# main.net
KiCad netlist of a schematic drawn in EAGLE
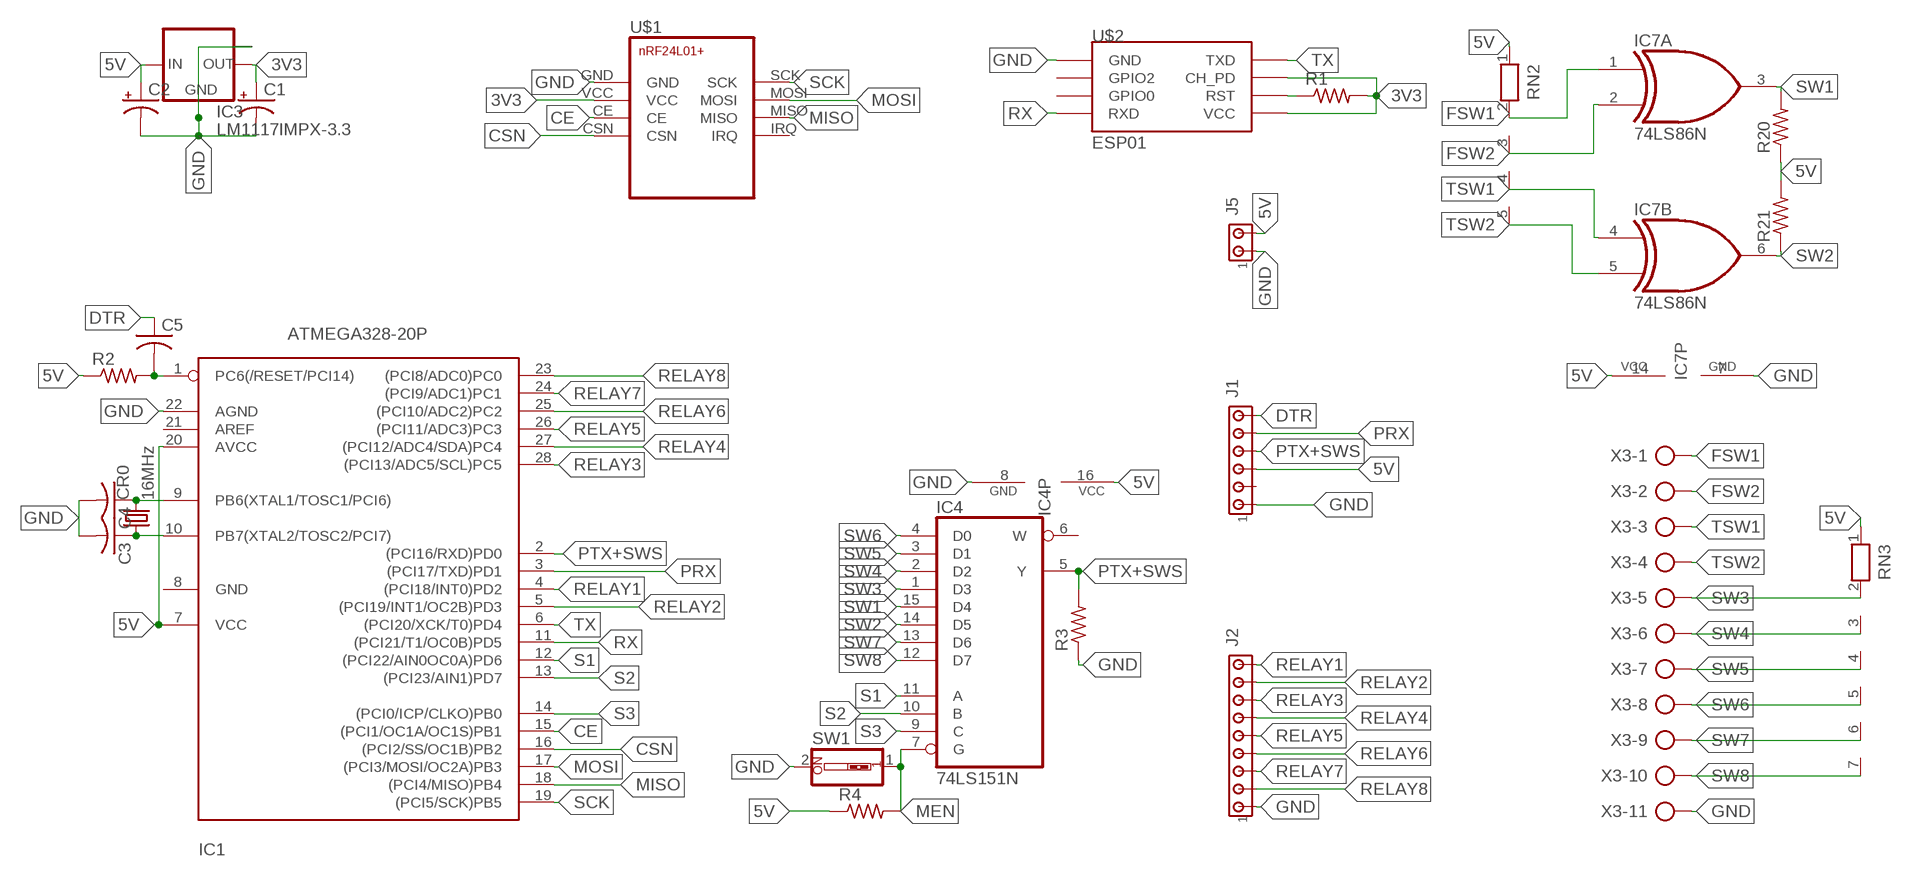
[diagram p0: schematic, sheet 1]
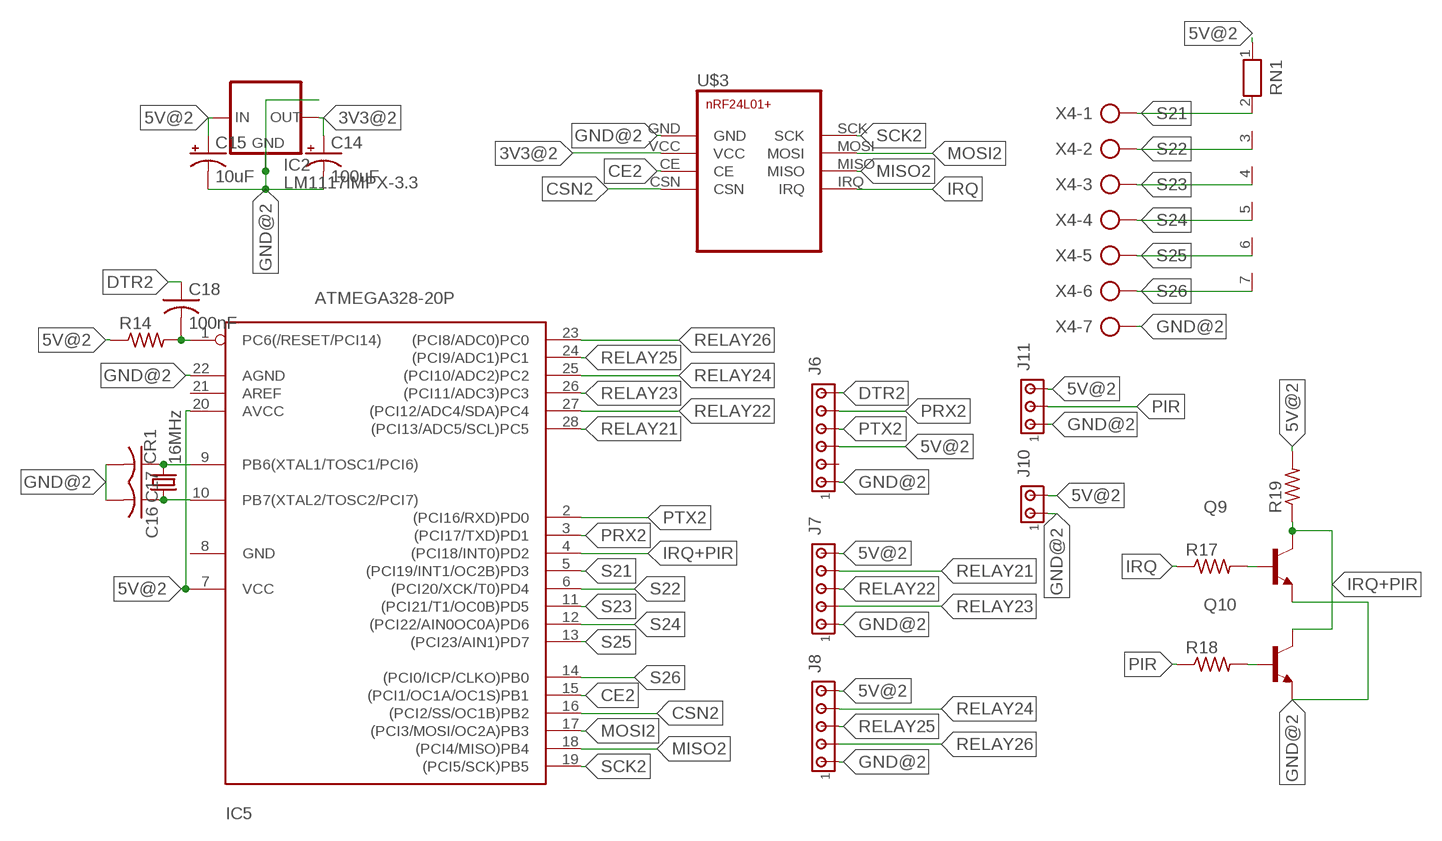
[diagram p1: schematic, sheet 2]
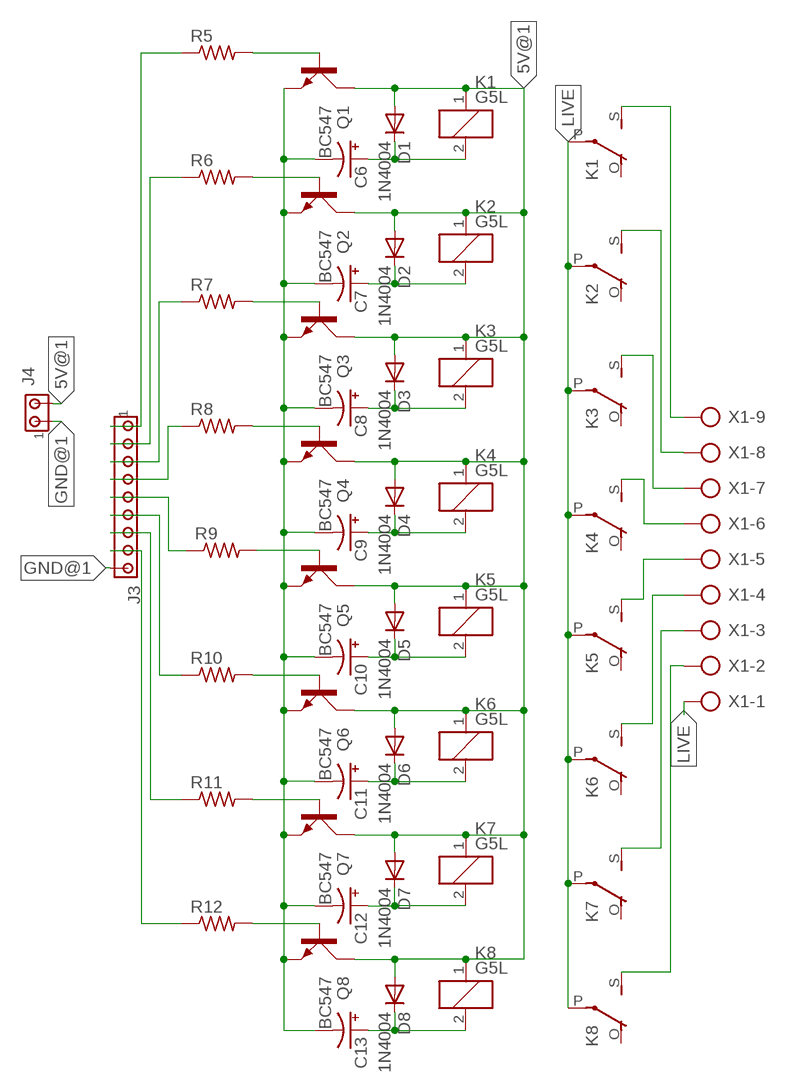
[diagram p2: schematic, sheet 3]
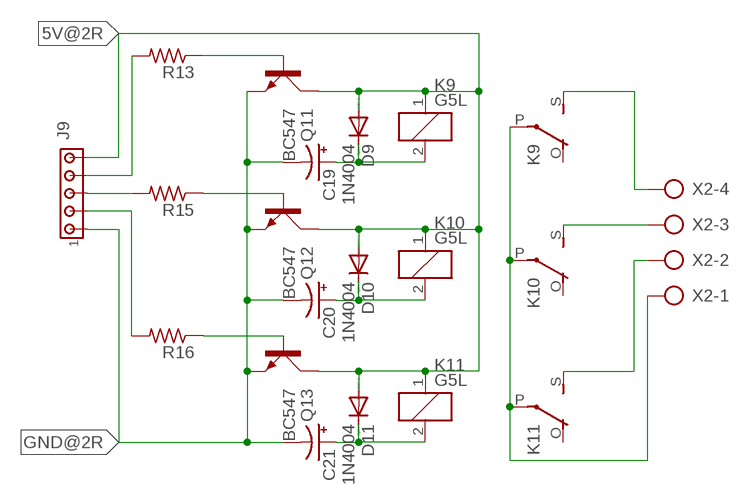
[diagram p3: schematic, sheet 4]

(export (version "E")
  (design (tool "Eeschema 10.0.6"))
  (components
    (comp (ref "C19")
      (value "CPOL-USE2.5-6")
      (footprint "eagle-import:E2,5-6")
      (libsource (lib "eagle-import") (part "CPOL-USE2.5-6"))
    )
    (comp (ref "C20")
      (value "CPOL-USE2.5-6")
      (footprint "eagle-import:E2,5-6")
      (libsource (lib "eagle-import") (part "CPOL-USE2.5-6"))
    )
    (comp (ref "C21")
      (value "CPOL-USE2.5-6")
      (footprint "eagle-import:E2,5-6")
      (libsource (lib "eagle-import") (part "CPOL-USE2.5-6"))
    )
    (comp (ref "D9")
      (value "1N4004")
      (footprint "eagle-import:DO41-10")
      (libsource (lib "eagle-import") (part "diode_210_1N4004"))
    )
    (comp (ref "D10")
      (value "1N4004")
      (footprint "eagle-import:DO41-10")
      (libsource (lib "eagle-import") (part "diode_210_1N4004"))
    )
    (comp (ref "D11")
      (value "1N4004")
      (footprint "eagle-import:DO41-10")
      (libsource (lib "eagle-import") (part "diode_210_1N4004"))
    )
    (comp (ref "J9")
      (value "MTA05-100")
      (footprint "eagle-import:10X05MTA")
      (libsource (lib "eagle-import") (part "MTA05-100"))
    )
    (comp (ref "K9")
      (value "G5L")
      (footprint "eagle-import:G5LE")
      (libsource (lib "eagle-import") (part "G5L"))
    )
    (comp (ref "K10")
      (value "G5L")
      (footprint "eagle-import:G5LE")
      (libsource (lib "eagle-import") (part "G5L"))
    )
    (comp (ref "K11")
      (value "G5L")
      (footprint "eagle-import:G5LE")
      (libsource (lib "eagle-import") (part "G5L"))
    )
    (comp (ref "Q11")
      (value "BC547")
      (footprint "eagle-import:SOT54A")
      (libsource (lib "eagle-import") (part "BC547"))
    )
    (comp (ref "Q12")
      (value "BC547")
      (footprint "eagle-import:SOT54A")
      (libsource (lib "eagle-import") (part "BC547"))
    )
    (comp (ref "Q13")
      (value "BC547")
      (footprint "eagle-import:SOT54A")
      (libsource (lib "eagle-import") (part "BC547"))
    )
    (comp (ref "R13")
      (value "R-US_0204/7")
      (footprint "eagle-import:0204_7")
      (libsource (lib "eagle-import") (part "R-US_0204/7"))
    )
    (comp (ref "R15")
      (value "R-US_0204/7")
      (footprint "eagle-import:0204_7")
      (libsource (lib "eagle-import") (part "R-US_0204/7"))
    )
    (comp (ref "R16")
      (value "R-US_0204/7")
      (footprint "eagle-import:0204_7")
      (libsource (lib "eagle-import") (part "R-US_0204/7"))
    )
    (comp (ref "X2")
      (value "AK300/4")
      (footprint "eagle-import:AK300_4")
      (libsource (lib "eagle-import") (part "AK300/4"))
    )
    (comp (ref "C6")
      (value "CPOL-USE2.5-6")
      (footprint "eagle-import:E2,5-6")
      (libsource (lib "eagle-import") (part "CPOL-USE2.5-6"))
    )
    (comp (ref "C7")
      (value "CPOL-USE2.5-6")
      (footprint "eagle-import:E2,5-6")
      (libsource (lib "eagle-import") (part "CPOL-USE2.5-6"))
    )
    (comp (ref "C8")
      (value "CPOL-USE2.5-6")
      (footprint "eagle-import:E2,5-6")
      (libsource (lib "eagle-import") (part "CPOL-USE2.5-6"))
    )
    (comp (ref "C9")
      (value "CPOL-USE2.5-6")
      (footprint "eagle-import:E2,5-6")
      (libsource (lib "eagle-import") (part "CPOL-USE2.5-6"))
    )
    (comp (ref "C10")
      (value "CPOL-USE2.5-6")
      (footprint "eagle-import:E2,5-6")
      (libsource (lib "eagle-import") (part "CPOL-USE2.5-6"))
    )
    (comp (ref "C11")
      (value "CPOL-USE2.5-6")
      (footprint "eagle-import:E2,5-6")
      (libsource (lib "eagle-import") (part "CPOL-USE2.5-6"))
    )
    (comp (ref "C12")
      (value "CPOL-USE2.5-6")
      (footprint "eagle-import:E2,5-6")
      (libsource (lib "eagle-import") (part "CPOL-USE2.5-6"))
    )
    (comp (ref "C13")
      (value "CPOL-USE2.5-6")
      (footprint "eagle-import:E2,5-6")
      (libsource (lib "eagle-import") (part "CPOL-USE2.5-6"))
    )
    (comp (ref "D1")
      (value "1N4004")
      (footprint "eagle-import:DO41-10")
      (libsource (lib "eagle-import") (part "1N4004"))
    )
    (comp (ref "D2")
      (value "1N4004")
      (footprint "eagle-import:DO41-10")
      (libsource (lib "eagle-import") (part "1N4004"))
    )
    (comp (ref "D3")
      (value "1N4004")
      (footprint "eagle-import:DO41-10")
      (libsource (lib "eagle-import") (part "1N4004"))
    )
    (comp (ref "D4")
      (value "1N4004")
      (footprint "eagle-import:DO41-10")
      (libsource (lib "eagle-import") (part "1N4004"))
    )
    (comp (ref "D5")
      (value "1N4004")
      (footprint "eagle-import:DO41-10")
      (libsource (lib "eagle-import") (part "1N4004"))
    )
    (comp (ref "D6")
      (value "1N4004")
      (footprint "eagle-import:DO41-10")
      (libsource (lib "eagle-import") (part "1N4004"))
    )
    (comp (ref "D7")
      (value "1N4004")
      (footprint "eagle-import:DO41-10")
      (libsource (lib "eagle-import") (part "1N4004"))
    )
    (comp (ref "D8")
      (value "1N4004")
      (footprint "eagle-import:DO41-10")
      (libsource (lib "eagle-import") (part "1N4004"))
    )
    (comp (ref "J3")
      (value "MTA09-100")
      (footprint "eagle-import:10X09MTA")
      (libsource (lib "eagle-import") (part "MTA09-100"))
    )
    (comp (ref "J4")
      (value "MTA02-100")
      (footprint "eagle-import:10X02MTA")
      (libsource (lib "eagle-import") (part "MTA02-100"))
    )
    (comp (ref "K1")
      (value "G5L")
      (footprint "eagle-import:G5LE")
      (libsource (lib "eagle-import") (part "G5L"))
    )
    (comp (ref "K2")
      (value "G5L")
      (footprint "eagle-import:G5LE")
      (libsource (lib "eagle-import") (part "G5L"))
    )
    (comp (ref "K3")
      (value "G5L")
      (footprint "eagle-import:G5LE")
      (libsource (lib "eagle-import") (part "G5L"))
    )
    (comp (ref "K4")
      (value "G5L")
      (footprint "eagle-import:G5LE")
      (libsource (lib "eagle-import") (part "G5L"))
    )
    (comp (ref "K5")
      (value "G5L")
      (footprint "eagle-import:G5LE")
      (libsource (lib "eagle-import") (part "G5L"))
    )
    (comp (ref "K6")
      (value "G5L")
      (footprint "eagle-import:G5LE")
      (libsource (lib "eagle-import") (part "G5L"))
    )
    (comp (ref "K7")
      (value "G5L")
      (footprint "eagle-import:G5LE")
      (libsource (lib "eagle-import") (part "G5L"))
    )
    (comp (ref "K8")
      (value "G5L")
      (footprint "eagle-import:G5LE")
      (libsource (lib "eagle-import") (part "G5L"))
    )
    (comp (ref "Q1")
      (value "BC547")
      (footprint "eagle-import:SOT54A")
      (libsource (lib "eagle-import") (part "BC547"))
    )
    (comp (ref "Q2")
      (value "BC547")
      (footprint "eagle-import:SOT54A")
      (libsource (lib "eagle-import") (part "BC547"))
    )
    (comp (ref "Q3")
      (value "BC547")
      (footprint "eagle-import:SOT54A")
      (libsource (lib "eagle-import") (part "BC547"))
    )
    (comp (ref "Q4")
      (value "BC547")
      (footprint "eagle-import:SOT54A")
      (libsource (lib "eagle-import") (part "BC547"))
    )
    (comp (ref "Q5")
      (value "BC547")
      (footprint "eagle-import:SOT54A")
      (libsource (lib "eagle-import") (part "BC547"))
    )
    (comp (ref "Q6")
      (value "BC547")
      (footprint "eagle-import:SOT54A")
      (libsource (lib "eagle-import") (part "BC547"))
    )
    (comp (ref "Q7")
      (value "BC547")
      (footprint "eagle-import:SOT54A")
      (libsource (lib "eagle-import") (part "BC547"))
    )
    (comp (ref "Q8")
      (value "BC547")
      (footprint "eagle-import:SOT54A")
      (libsource (lib "eagle-import") (part "BC547"))
    )
    (comp (ref "R5")
      (value "R-US_0204/7")
      (footprint "eagle-import:0204_7")
      (libsource (lib "eagle-import") (part "R-US_0204/7"))
    )
    (comp (ref "R6")
      (value "R-US_0204/7")
      (footprint "eagle-import:0204_7")
      (libsource (lib "eagle-import") (part "R-US_0204/7"))
    )
    (comp (ref "R7")
      (value "R-US_0204/7")
      (footprint "eagle-import:0204_7")
      (libsource (lib "eagle-import") (part "R-US_0204/7"))
    )
    (comp (ref "R8")
      (value "R-US_0204/7")
      (footprint "eagle-import:0204_7")
      (libsource (lib "eagle-import") (part "R-US_0204/7"))
    )
    (comp (ref "R9")
      (value "R-US_0204/7")
      (footprint "eagle-import:0204_7")
      (libsource (lib "eagle-import") (part "R-US_0204/7"))
    )
    (comp (ref "R10")
      (value "R-US_0204/7")
      (footprint "eagle-import:0204_7")
      (libsource (lib "eagle-import") (part "R-US_0204/7"))
    )
    (comp (ref "R11")
      (value "R-US_0204/7")
      (footprint "eagle-import:0204_7")
      (libsource (lib "eagle-import") (part "R-US_0204/7"))
    )
    (comp (ref "R12")
      (value "R-US_0204/7")
      (footprint "eagle-import:0204_7")
      (libsource (lib "eagle-import") (part "R-US_0204/7"))
    )
    (comp (ref "X1")
      (value "AK300/9")
      (footprint "eagle-import:AK300_9")
      (libsource (lib "eagle-import") (part "AK300/9"))
    )
    (comp (ref "C1")
      (value "CPOL-USE2,5-6E")
      (footprint "eagle-import:E2,5-6E")
      (libsource (lib "eagle-import") (part "CPOL-USE2,5-6E"))
    )
    (comp (ref "C2")
      (value "CPOL-USE2,5-6E")
      (footprint "eagle-import:E2,5-6E")
      (libsource (lib "eagle-import") (part "CPOL-USE2,5-6E"))
    )
    (comp (ref "C3")
      (value "C-USC1206")
      (footprint "eagle-import:C1206")
      (libsource (lib "eagle-import") (part "C-USC1206"))
    )
    (comp (ref "C4")
      (value "C-USC1206")
      (footprint "eagle-import:C1206")
      (libsource (lib "eagle-import") (part "C-USC1206"))
    )
    (comp (ref "C5")
      (value "C-USC1206")
      (footprint "eagle-import:C1206")
      (libsource (lib "eagle-import") (part "C-USC1206"))
    )
    (comp (ref "CR0")
      (value "16MHz")
      (footprint "eagle-import:HC18U-V")
      (libsource (lib "eagle-import") (part "CRYSTALHC18U-V"))
    )
    (comp (ref "IC1")
      (value "ATMEGA328-20P")
      (footprint "eagle-import:DIL28-3")
      (libsource (lib "eagle-import") (part "ATMEGA328P-20"))
    )
    (comp (ref "IC3")
      (value "LM1117IMPX-3.3")
      (footprint "eagle-import:SOT223")
      (libsource (lib "eagle-import") (part "LM1117IMPX-3.3"))
    )
    (comp (ref "IC4")
      (value "74LS151N")
      (footprint "eagle-import:DIL16")
      (libsource (lib "eagle-import") (part "74151NLS"))
    )
    (comp (ref "IC7")
      (value "74LS86N")
      (footprint "eagle-import:DIL14")
      (libsource (lib "eagle-import") (part "7486NLS"))
    )
    (comp (ref "J1")
      (value "MTA06-100")
      (footprint "eagle-import:10X06MTA")
      (libsource (lib "eagle-import") (part "MTA06-100"))
    )
    (comp (ref "J2")
      (value "MTA09-100")
      (footprint "eagle-import:10X09MTA")
      (libsource (lib "eagle-import") (part "MTA09-100"))
    )
    (comp (ref "J5")
      (value "MTA02-100")
      (footprint "eagle-import:10X02MTA")
      (libsource (lib "eagle-import") (part "MTA02-100"))
    )
    (comp (ref "R1")
      (value "R-US_R1206")
      (footprint "eagle-import:R1206")
      (libsource (lib "eagle-import") (part "R-US_R1206"))
    )
    (comp (ref "R2")
      (value "R-US_R1206")
      (footprint "eagle-import:R1206")
      (libsource (lib "eagle-import") (part "R-US_R1206"))
    )
    (comp (ref "R3")
      (value "R-US_R1206")
      (footprint "eagle-import:R1206")
      (libsource (lib "eagle-import") (part "R-US_R1206"))
    )
    (comp (ref "R4")
      (value "R-US_R1206")
      (footprint "eagle-import:R1206")
      (libsource (lib "eagle-import") (part "R-US_R1206"))
    )
    (comp (ref "R20")
      (value "R-US_0204/7")
      (footprint "eagle-import:0204_7")
      (libsource (lib "eagle-import") (part "R-US_0204/7"))
    )
    (comp (ref "R21")
      (value "R-US_R1206")
      (footprint "eagle-import:R1206")
      (libsource (lib "eagle-import") (part "R-US_R1206"))
    )
    (comp (ref "RN2")
      (value "RN04")
      (footprint "eagle-import:RN-5")
      (libsource (lib "eagle-import") (part "RN04"))
    )
    (comp (ref "RN3")
      (value "RN06")
      (footprint "eagle-import:RN-7")
      (libsource (lib "eagle-import") (part "RN06"))
    )
    (comp (ref "SW1")
      (value "SW_DIP-1")
      (footprint "eagle-import:EDG-01")
      (libsource (lib "eagle-import") (part "SW_DIP-1"))
    )
    (comp (ref "U$1")
      (value "NRF24L01+")
      (footprint "eagle-import:NRF24L01+")
      (libsource (lib "eagle-import") (part "NRF24L01+"))
    )
    (comp (ref "U$2")
      (value "ESP01")
      (footprint "eagle-import:ESP01")
      (libsource (lib "eagle-import") (part "ESP01"))
    )
    (comp (ref "X3")
      (value "AK300/11")
      (footprint "eagle-import:AK300_11")
      (libsource (lib "eagle-import") (part "AK300/11"))
    )
    (comp (ref "C14")
      (value "100uF")
      (footprint "eagle-import:E2,5-6E")
      (libsource (lib "eagle-import") (part "CPOL-USE2,5-6E"))
    )
    (comp (ref "C15")
      (value "10uF")
      (footprint "eagle-import:E2,5-6E")
      (libsource (lib "eagle-import") (part "CPOL-USE2,5-6E"))
    )
    (comp (ref "C16")
      (value "C-USC1206")
      (footprint "eagle-import:C1206")
      (libsource (lib "eagle-import") (part "C-USC1206"))
    )
    (comp (ref "C17")
      (value "C-USC1206")
      (footprint "eagle-import:C1206")
      (libsource (lib "eagle-import") (part "C-USC1206"))
    )
    (comp (ref "C18")
      (value "100nF")
      (footprint "eagle-import:C1206")
      (libsource (lib "eagle-import") (part "C-USC1206"))
    )
    (comp (ref "CR1")
      (value "16MHz")
      (footprint "eagle-import:HC18U-V")
      (libsource (lib "eagle-import") (part "CRYSTALHC18U-V"))
    )
    (comp (ref "IC2")
      (value "LM1117IMPX-3.3")
      (footprint "eagle-import:SOT223")
      (libsource (lib "eagle-import") (part "LM1117IMPX-3.3"))
    )
    (comp (ref "IC5")
      (value "ATMEGA328-20P")
      (footprint "eagle-import:DIL28-3")
      (libsource (lib "eagle-import") (part "ATMEGA328P-20"))
    )
    (comp (ref "J6")
      (value "MTA06-100")
      (footprint "eagle-import:10X06MTA")
      (libsource (lib "eagle-import") (part "MTA06-100"))
    )
    (comp (ref "J7")
      (value "MTA05-100")
      (footprint "eagle-import:10X05MTA")
      (libsource (lib "eagle-import") (part "MTA05-100"))
    )
    (comp (ref "J8")
      (value "MTA05-100")
      (footprint "eagle-import:10X05MTA")
      (libsource (lib "eagle-import") (part "MTA05-100"))
    )
    (comp (ref "J10")
      (value "MTA02-100")
      (footprint "eagle-import:10X02MTA")
      (libsource (lib "eagle-import") (part "MTA02-100"))
    )
    (comp (ref "J11")
      (value "MTA03-100")
      (footprint "eagle-import:10X03MTA")
      (libsource (lib "eagle-import") (part "MTA03-100"))
    )
    (comp (ref "Q9")
      (value "-NPN-SOT89-BCE")
      (footprint "eagle-import:SOT89-BCE")
      (libsource (lib "eagle-import") (part "-NPN-SOT89-BCE"))
    )
    (comp (ref "Q10")
      (value "-NPN-SOT89-BCE")
      (footprint "eagle-import:SOT89-BCE")
      (libsource (lib "eagle-import") (part "-NPN-SOT89-BCE"))
    )
    (comp (ref "R14")
      (value "R-US_R1206")
      (footprint "eagle-import:R1206")
      (libsource (lib "eagle-import") (part "R-US_R1206"))
    )
    (comp (ref "R17")
      (value "R-US_R1206")
      (footprint "eagle-import:R1206")
      (libsource (lib "eagle-import") (part "R-US_R1206"))
    )
    (comp (ref "R18")
      (value "R-US_R1206")
      (footprint "eagle-import:R1206")
      (libsource (lib "eagle-import") (part "R-US_R1206"))
    )
    (comp (ref "R19")
      (value "R-US_R1206")
      (footprint "eagle-import:R1206")
      (libsource (lib "eagle-import") (part "R-US_R1206"))
    )
    (comp (ref "RN1")
      (value "RN06")
      (footprint "eagle-import:RN-7")
      (libsource (lib "eagle-import") (part "RN06"))
    )
    (comp (ref "U$3")
      (value "NRF24L01+")
      (footprint "eagle-import:NRF24L01+")
      (libsource (lib "eagle-import") (part "NRF24L01+"))
    )
    (comp (ref "X4")
      (value "AK300/7")
      (footprint "eagle-import:AK300_7")
      (libsource (lib "eagle-import") (part "AK300/7"))
    )
  )
  (nets
    (net (code "1") (name "3V3") (class "Default")
      (node (ref "C1") (pin "+") (pinfunction "+_+") (pintype "passive"))
      (node (ref "IC3") (pin "2") (pinfunction "OUT_2") (pintype "passive"))
      (node (ref "R1") (pin "2") (pinfunction "2_2") (pintype "passive"))
      (node (ref "U$1") (pin "VCC") (pinfunction "VCC_VCC") (pintype "power_in"))
      (node (ref "U$2") (pin "CH_PD") (pinfunction "CH_PD_CH_PD") (pintype "bidirectional"))
      (node (ref "U$2") (pin "VCC") (pinfunction "VCC_VCC") (pintype "bidirectional"))
    )
    (net (code "2") (name "3V3@2") (class "Default")
      (node (ref "C14") (pin "+") (pinfunction "+_+") (pintype "passive"))
      (node (ref "IC2") (pin "2") (pinfunction "OUT_2") (pintype "passive"))
      (node (ref "U$3") (pin "VCC") (pinfunction "VCC_VCC") (pintype "power_in"))
    )
    (net (code "3") (name "5V") (class "Default")
      (node (ref "C2") (pin "+") (pinfunction "+_+") (pintype "passive"))
      (node (ref "IC1") (pin "20") (pinfunction "AVCC_20") (pintype "bidirectional"))
      (node (ref "IC1") (pin "7") (pinfunction "VCC_7") (pintype "bidirectional"))
      (node (ref "IC3") (pin "3") (pinfunction "IN_3") (pintype "input"))
      (node (ref "IC4") (pin "16") (pinfunction "VCC_16") (pintype "power_in"))
      (node (ref "IC7") (pin "14") (pinfunction "VCC_14") (pintype "power_in"))
      (node (ref "J1") (pin "3") (pinfunction "3_3") (pintype "passive"))
      (node (ref "J5") (pin "2") (pinfunction "2_2") (pintype "passive"))
      (node (ref "R2") (pin "1") (pinfunction "1_1") (pintype "passive"))
      (node (ref "R20") (pin "1") (pinfunction "1_1") (pintype "passive"))
      (node (ref "R21") (pin "2") (pinfunction "2_2") (pintype "passive"))
      (node (ref "R4") (pin "1") (pinfunction "1_1") (pintype "passive"))
      (node (ref "RN2") (pin "1") (pinfunction "1_1") (pintype "passive"))
      (node (ref "RN3") (pin "1") (pinfunction "1_1") (pintype "passive"))
    )
    (net (code "4") (name "5V@1") (class "Default")
      (node (ref "D1") (pin "A") (pinfunction "A_A") (pintype "passive"))
      (node (ref "D2") (pin "A") (pinfunction "A_A") (pintype "passive"))
      (node (ref "D3") (pin "A") (pinfunction "A_A") (pintype "passive"))
      (node (ref "D4") (pin "A") (pinfunction "A_A") (pintype "passive"))
      (node (ref "D5") (pin "A") (pinfunction "A_A") (pintype "passive"))
      (node (ref "D6") (pin "A") (pinfunction "A_A") (pintype "passive"))
      (node (ref "D7") (pin "A") (pinfunction "A_A") (pintype "passive"))
      (node (ref "D8") (pin "A") (pinfunction "A_A") (pintype "passive"))
      (node (ref "J4") (pin "2") (pinfunction "2_2") (pintype "passive"))
      (node (ref "K1") (pin "1") (pinfunction "1_1") (pintype "passive"))
      (node (ref "K2") (pin "1") (pinfunction "1_1") (pintype "passive"))
      (node (ref "K3") (pin "1") (pinfunction "1_1") (pintype "passive"))
      (node (ref "K4") (pin "1") (pinfunction "1_1") (pintype "passive"))
      (node (ref "K5") (pin "1") (pinfunction "1_1") (pintype "passive"))
      (node (ref "K6") (pin "1") (pinfunction "1_1") (pintype "passive"))
      (node (ref "K7") (pin "1") (pinfunction "1_1") (pintype "passive"))
      (node (ref "K8") (pin "1") (pinfunction "1_1") (pintype "passive"))
      (node (ref "Q1") (pin "C") (pinfunction "C_C") (pintype "passive"))
      (node (ref "Q2") (pin "C") (pinfunction "C_C") (pintype "passive"))
      (node (ref "Q3") (pin "C") (pinfunction "C_C") (pintype "passive"))
      (node (ref "Q4") (pin "C") (pinfunction "C_C") (pintype "passive"))
      (node (ref "Q5") (pin "C") (pinfunction "C_C") (pintype "passive"))
      (node (ref "Q6") (pin "C") (pinfunction "C_C") (pintype "passive"))
      (node (ref "Q7") (pin "C") (pinfunction "C_C") (pintype "passive"))
      (node (ref "Q8") (pin "C") (pinfunction "C_C") (pintype "passive"))
    )
    (net (code "5") (name "5V@2") (class "Default")
      (node (ref "C15") (pin "+") (pinfunction "+_+") (pintype "passive"))
      (node (ref "IC2") (pin "3") (pinfunction "IN_3") (pintype "input"))
      (node (ref "IC5") (pin "20") (pinfunction "AVCC_20") (pintype "bidirectional"))
      (node (ref "IC5") (pin "7") (pinfunction "VCC_7") (pintype "bidirectional"))
      (node (ref "J10") (pin "2") (pinfunction "2_2") (pintype "passive"))
      (node (ref "J11") (pin "3") (pinfunction "3_3") (pintype "passive"))
      (node (ref "J6") (pin "3") (pinfunction "3_3") (pintype "passive"))
      (node (ref "J7") (pin "5") (pinfunction "5_5") (pintype "passive"))
      (node (ref "J8") (pin "5") (pinfunction "5_5") (pintype "passive"))
      (node (ref "R14") (pin "1") (pinfunction "1_1") (pintype "passive"))
      (node (ref "R19") (pin "2") (pinfunction "2_2") (pintype "passive"))
      (node (ref "RN1") (pin "1") (pinfunction "1_1") (pintype "passive"))
    )
    (net (code "6") (name "5V@2R") (class "Default")
      (node (ref "D10") (pin "A") (pinfunction "A_A") (pintype "passive"))
      (node (ref "D11") (pin "A") (pinfunction "A_A") (pintype "passive"))
      (node (ref "D9") (pin "A") (pinfunction "A_A") (pintype "passive"))
      (node (ref "J9") (pin "5") (pinfunction "5_5") (pintype "passive"))
      (node (ref "K10") (pin "1") (pinfunction "1_1") (pintype "passive"))
      (node (ref "K11") (pin "1") (pinfunction "1_1") (pintype "passive"))
      (node (ref "K9") (pin "1") (pinfunction "1_1") (pintype "passive"))
      (node (ref "Q11") (pin "C") (pinfunction "C_C") (pintype "passive"))
      (node (ref "Q12") (pin "C") (pinfunction "C_C") (pintype "passive"))
      (node (ref "Q13") (pin "C") (pinfunction "C_C") (pintype "passive"))
    )
    (net (code "7") (name "CE") (class "Default")
      (node (ref "IC1") (pin "15") (pinfunction "(PCI1/OC1A/OC1S)PB1_15") (pintype "bidirectional"))
      (node (ref "U$1") (pin "CE") (pinfunction "CE_CE") (pintype "bidirectional"))
    )
    (net (code "8") (name "CE2") (class "Default")
      (node (ref "IC5") (pin "15") (pinfunction "(PCI1/OC1A/OC1S)PB1_15") (pintype "bidirectional"))
      (node (ref "U$3") (pin "CE") (pinfunction "CE_CE") (pintype "bidirectional"))
    )
    (net (code "9") (name "CSN") (class "Default")
      (node (ref "IC1") (pin "16") (pinfunction "(PCI2/SS/OC1B)PB2_16") (pintype "bidirectional"))
      (node (ref "U$1") (pin "CSN") (pinfunction "CSN_CSN") (pintype "bidirectional"))
    )
    (net (code "10") (name "CSN2") (class "Default")
      (node (ref "IC5") (pin "16") (pinfunction "(PCI2/SS/OC1B)PB2_16") (pintype "bidirectional"))
      (node (ref "U$3") (pin "CSN") (pinfunction "CSN_CSN") (pintype "bidirectional"))
    )
    (net (code "11") (name "DTR") (class "Default")
      (node (ref "C5") (pin "1") (pinfunction "1_1") (pintype "passive"))
      (node (ref "J1") (pin "6") (pinfunction "6_6") (pintype "passive"))
    )
    (net (code "12") (name "DTR2") (class "Default")
      (node (ref "C18") (pin "1") (pinfunction "1_1") (pintype "passive"))
      (node (ref "J6") (pin "6") (pinfunction "6_6") (pintype "passive"))
    )
    (net (code "13") (name "FSW1") (class "Default")
      (node (ref "IC7") (pin "1") (pinfunction "I0_1") (pintype "input"))
      (node (ref "RN2") (pin "2") (pinfunction "2_2") (pintype "passive"))
      (node (ref "X3") (pin "1") (pinfunction "KL_1") (pintype "passive"))
    )
    (net (code "14") (name "FSW2") (class "Default")
      (node (ref "IC7") (pin "2") (pinfunction "I1_2") (pintype "input"))
      (node (ref "RN2") (pin "3") (pinfunction "3_3") (pintype "passive"))
      (node (ref "X3") (pin "2") (pinfunction "KL_2") (pintype "passive"))
    )
    (net (code "15") (name "GND") (class "Default")
      (node (ref "C1") (pin "-") (pinfunction "-_-") (pintype "passive"))
      (node (ref "C2") (pin "-") (pinfunction "-_-") (pintype "passive"))
      (node (ref "C3") (pin "2") (pinfunction "2_2") (pintype "passive"))
      (node (ref "C4") (pin "2") (pinfunction "2_2") (pintype "passive"))
      (node (ref "IC1") (pin "22") (pinfunction "AGND_22") (pintype "bidirectional"))
      (node (ref "IC3") (pin "1") (pinfunction "GND_1") (pintype "input"))
      (node (ref "IC3") (pin "TAB") (pinfunction "OUT1_TAB") (pintype "passive"))
      (node (ref "IC4") (pin "8") (pinfunction "GND_8") (pintype "power_in"))
      (node (ref "IC7") (pin "7") (pinfunction "GND_7") (pintype "power_in"))
      (node (ref "J1") (pin "1") (pinfunction "1_1") (pintype "passive"))
      (node (ref "J2") (pin "1") (pinfunction "1_1") (pintype "passive"))
      (node (ref "J5") (pin "1") (pinfunction "1_1") (pintype "passive"))
      (node (ref "R3") (pin "1") (pinfunction "1_1") (pintype "passive"))
      (node (ref "SW1") (pin "2") (pinfunction "2_2") (pintype "passive"))
      (node (ref "U$1") (pin "GND") (pinfunction "GND_GND") (pintype "power_in"))
      (node (ref "U$2") (pin "GND") (pinfunction "GND_GND") (pintype "bidirectional"))
      (node (ref "X3") (pin "11") (pinfunction "KL_11") (pintype "passive"))
    )
    (net (code "16") (name "GND@1") (class "Default")
      (node (ref "C10") (pin "-") (pinfunction "-_-") (pintype "passive"))
      (node (ref "C11") (pin "-") (pinfunction "-_-") (pintype "passive"))
      (node (ref "C12") (pin "-") (pinfunction "-_-") (pintype "passive"))
      (node (ref "C13") (pin "-") (pinfunction "-_-") (pintype "passive"))
      (node (ref "C6") (pin "-") (pinfunction "-_-") (pintype "passive"))
      (node (ref "C7") (pin "-") (pinfunction "-_-") (pintype "passive"))
      (node (ref "C8") (pin "-") (pinfunction "-_-") (pintype "passive"))
      (node (ref "C9") (pin "-") (pinfunction "-_-") (pintype "passive"))
      (node (ref "J3") (pin "9") (pinfunction "9_9") (pintype "passive"))
      (node (ref "J4") (pin "1") (pinfunction "1_1") (pintype "passive"))
      (node (ref "Q1") (pin "E") (pinfunction "E_E") (pintype "passive"))
      (node (ref "Q2") (pin "E") (pinfunction "E_E") (pintype "passive"))
      (node (ref "Q3") (pin "E") (pinfunction "E_E") (pintype "passive"))
      (node (ref "Q4") (pin "E") (pinfunction "E_E") (pintype "passive"))
      (node (ref "Q5") (pin "E") (pinfunction "E_E") (pintype "passive"))
      (node (ref "Q6") (pin "E") (pinfunction "E_E") (pintype "passive"))
      (node (ref "Q7") (pin "E") (pinfunction "E_E") (pintype "passive"))
      (node (ref "Q8") (pin "E") (pinfunction "E_E") (pintype "passive"))
    )
    (net (code "17") (name "GND@2") (class "Default")
      (node (ref "C14") (pin "-") (pinfunction "-_-") (pintype "passive"))
      (node (ref "C15") (pin "-") (pinfunction "-_-") (pintype "passive"))
      (node (ref "C16") (pin "2") (pinfunction "2_2") (pintype "passive"))
      (node (ref "C17") (pin "2") (pinfunction "2_2") (pintype "passive"))
      (node (ref "IC2") (pin "1") (pinfunction "GND_1") (pintype "input"))
      (node (ref "IC2") (pin "TAB") (pinfunction "OUT1_TAB") (pintype "passive"))
      (node (ref "IC5") (pin "22") (pinfunction "AGND_22") (pintype "bidirectional"))
      (node (ref "J10") (pin "1") (pinfunction "1_1") (pintype "passive"))
      (node (ref "J11") (pin "1") (pinfunction "1_1") (pintype "passive"))
      (node (ref "J6") (pin "1") (pinfunction "1_1") (pintype "passive"))
      (node (ref "J7") (pin "1") (pinfunction "1_1") (pintype "passive"))
      (node (ref "J8") (pin "1") (pinfunction "1_1") (pintype "passive"))
      (node (ref "Q10") (pin "E") (pinfunction "E_E") (pintype "passive"))
      (node (ref "Q9") (pin "E") (pinfunction "E_E") (pintype "passive"))
      (node (ref "U$3") (pin "GND") (pinfunction "GND_GND") (pintype "power_in"))
      (node (ref "X4") (pin "7") (pinfunction "KL_7") (pintype "passive"))
    )
    (net (code "18") (name "GND@2R") (class "Default")
      (node (ref "C19") (pin "-") (pinfunction "-_-") (pintype "passive"))
      (node (ref "C20") (pin "-") (pinfunction "-_-") (pintype "passive"))
      (node (ref "C21") (pin "-") (pinfunction "-_-") (pintype "passive"))
      (node (ref "J9") (pin "1") (pinfunction "1_1") (pintype "passive"))
      (node (ref "Q11") (pin "E") (pinfunction "E_E") (pintype "passive"))
      (node (ref "Q12") (pin "E") (pinfunction "E_E") (pintype "passive"))
      (node (ref "Q13") (pin "E") (pinfunction "E_E") (pintype "passive"))
    )
    (net (code "19") (name "IRQ") (class "Default")
      (node (ref "R17") (pin "1") (pinfunction "1_1") (pintype "passive"))
      (node (ref "U$3") (pin "IRQ") (pinfunction "IRQ_IRQ") (pintype "bidirectional"))
    )
    (net (code "20") (name "IRQ+PIR") (class "Default")
      (node (ref "IC5") (pin "4") (pinfunction "(PCI18/INT0)PD2_4") (pintype "bidirectional"))
      (node (ref "Q10") (pin "C") (pinfunction "C_C") (pintype "passive"))
      (node (ref "Q9") (pin "C") (pinfunction "C_C") (pintype "passive"))
      (node (ref "R19") (pin "1") (pinfunction "1_1") (pintype "passive"))
    )
    (net (code "21") (name "LIVE") (class "Default")
      (node (ref "K1") (pin "P") (pinfunction "P_P") (pintype "passive"))
      (node (ref "K2") (pin "P") (pinfunction "P_P") (pintype "passive"))
      (node (ref "K3") (pin "P") (pinfunction "P_P") (pintype "passive"))
      (node (ref "K4") (pin "P") (pinfunction "P_P") (pintype "passive"))
      (node (ref "K5") (pin "P") (pinfunction "P_P") (pintype "passive"))
      (node (ref "K6") (pin "P") (pinfunction "P_P") (pintype "passive"))
      (node (ref "K7") (pin "P") (pinfunction "P_P") (pintype "passive"))
      (node (ref "K8") (pin "P") (pinfunction "P_P") (pintype "passive"))
      (node (ref "X1") (pin "1") (pinfunction "KL_1") (pintype "passive"))
    )
    (net (code "22") (name "MEN") (class "Default")
      (node (ref "IC4") (pin "7") (pinfunction "G_7") (pintype "input"))
      (node (ref "R4") (pin "2") (pinfunction "2_2") (pintype "passive"))
      (node (ref "SW1") (pin "1") (pinfunction "1_1") (pintype "passive"))
    )
    (net (code "23") (name "MISO") (class "Default")
      (node (ref "IC1") (pin "18") (pinfunction "(PCI4/MISO)PB4_18") (pintype "bidirectional"))
      (node (ref "U$1") (pin "MISO") (pinfunction "MISO_MISO") (pintype "bidirectional"))
    )
    (net (code "24") (name "MISO2") (class "Default")
      (node (ref "IC5") (pin "18") (pinfunction "(PCI4/MISO)PB4_18") (pintype "bidirectional"))
      (node (ref "U$3") (pin "MISO") (pinfunction "MISO_MISO") (pintype "bidirectional"))
    )
    (net (code "25") (name "MOSI") (class "Default")
      (node (ref "IC1") (pin "17") (pinfunction "(PCI3/MOSI/OC2A)PB3_17") (pintype "bidirectional"))
      (node (ref "U$1") (pin "MOSI") (pinfunction "MOSI_MOSI") (pintype "bidirectional"))
    )
    (net (code "26") (name "MOSI2") (class "Default")
      (node (ref "IC5") (pin "17") (pinfunction "(PCI3/MOSI/OC2A)PB3_17") (pintype "bidirectional"))
      (node (ref "U$3") (pin "MOSI") (pinfunction "MOSI_MOSI") (pintype "bidirectional"))
    )
    (net (code "27") (name "Net-(C6-Pad+)") (class "Default")
      (node (ref "C6") (pin "+") (pinfunction "+_+") (pintype "passive"))
      (node (ref "D1") (pin "C") (pinfunction "C_C") (pintype "passive"))
      (node (ref "K1") (pin "2") (pinfunction "2_2") (pintype "passive"))
    )
    (net (code "28") (name "Net-(C7-Pad+)") (class "Default")
      (node (ref "C7") (pin "+") (pinfunction "+_+") (pintype "passive"))
      (node (ref "D2") (pin "C") (pinfunction "C_C") (pintype "passive"))
      (node (ref "K2") (pin "2") (pinfunction "2_2") (pintype "passive"))
    )
    (net (code "29") (name "Net-(C8-Pad+)") (class "Default")
      (node (ref "C8") (pin "+") (pinfunction "+_+") (pintype "passive"))
      (node (ref "D3") (pin "C") (pinfunction "C_C") (pintype "passive"))
      (node (ref "K3") (pin "2") (pinfunction "2_2") (pintype "passive"))
    )
    (net (code "30") (name "Net-(C9-Pad+)") (class "Default")
      (node (ref "C9") (pin "+") (pinfunction "+_+") (pintype "passive"))
      (node (ref "D4") (pin "C") (pinfunction "C_C") (pintype "passive"))
      (node (ref "K4") (pin "2") (pinfunction "2_2") (pintype "passive"))
    )
    (net (code "31") (name "Net-(C10-Pad+)") (class "Default")
      (node (ref "C10") (pin "+") (pinfunction "+_+") (pintype "passive"))
      (node (ref "D5") (pin "C") (pinfunction "C_C") (pintype "passive"))
      (node (ref "K5") (pin "2") (pinfunction "2_2") (pintype "passive"))
    )
    (net (code "32") (name "Net-(C11-Pad+)") (class "Default")
      (node (ref "C11") (pin "+") (pinfunction "+_+") (pintype "passive"))
      (node (ref "D6") (pin "C") (pinfunction "C_C") (pintype "passive"))
      (node (ref "K6") (pin "2") (pinfunction "2_2") (pintype "passive"))
    )
    (net (code "33") (name "Net-(C12-Pad+)") (class "Default")
      (node (ref "C12") (pin "+") (pinfunction "+_+") (pintype "passive"))
      (node (ref "D7") (pin "C") (pinfunction "C_C") (pintype "passive"))
      (node (ref "K7") (pin "2") (pinfunction "2_2") (pintype "passive"))
    )
    (net (code "34") (name "Net-(C13-Pad+)") (class "Default")
      (node (ref "C13") (pin "+") (pinfunction "+_+") (pintype "passive"))
      (node (ref "D8") (pin "C") (pinfunction "C_C") (pintype "passive"))
      (node (ref "K8") (pin "2") (pinfunction "2_2") (pintype "passive"))
    )
    (net (code "35") (name "Net-(C19-Pad+)") (class "Default")
      (node (ref "C19") (pin "+") (pinfunction "+_+") (pintype "passive"))
      (node (ref "D9") (pin "C") (pinfunction "C_C") (pintype "passive"))
      (node (ref "K9") (pin "2") (pinfunction "2_2") (pintype "passive"))
    )
    (net (code "36") (name "Net-(C20-Pad+)") (class "Default")
      (node (ref "C20") (pin "+") (pinfunction "+_+") (pintype "passive"))
      (node (ref "D10") (pin "C") (pinfunction "C_C") (pintype "passive"))
      (node (ref "K10") (pin "2") (pinfunction "2_2") (pintype "passive"))
    )
    (net (code "37") (name "Net-(C21-Pad+)") (class "Default")
      (node (ref "C21") (pin "+") (pinfunction "+_+") (pintype "passive"))
      (node (ref "D11") (pin "C") (pinfunction "C_C") (pintype "passive"))
      (node (ref "K11") (pin "2") (pinfunction "2_2") (pintype "passive"))
    )
    (net (code "38") (name "Net-(IC1-PB6(XTAL1{slash}TOSC1{slash}PCI6))") (class "Default")
      (node (ref "C4") (pin "1") (pinfunction "1_1") (pintype "passive"))
      (node (ref "CR0") (pin "2") (pinfunction "2_2") (pintype "passive"))
      (node (ref "IC1") (pin "9") (pinfunction "PB6(XTAL1/TOSC1/PCI6)_9") (pintype "bidirectional"))
    )
    (net (code "39") (name "Net-(IC1-PB7(XTAL2{slash}TOSC2{slash}PCI7))") (class "Default")
      (node (ref "C3") (pin "1") (pinfunction "1_1") (pintype "passive"))
      (node (ref "CR0") (pin "1") (pinfunction "1_1") (pintype "passive"))
      (node (ref "IC1") (pin "10") (pinfunction "PB7(XTAL2/TOSC2/PCI7)_10") (pintype "bidirectional"))
    )
    (net (code "40") (name "Net-(IC1-PC6({slash}RESET{slash}PCI14))") (class "Default")
      (node (ref "C5") (pin "2") (pinfunction "2_2") (pintype "passive"))
      (node (ref "IC1") (pin "1") (pinfunction "PC6(/RESET/PCI14)_1") (pintype "bidirectional"))
      (node (ref "R2") (pin "2") (pinfunction "2_2") (pintype "passive"))
    )
    (net (code "41") (name "Net-(IC5-PB6(XTAL1{slash}TOSC1{slash}PCI6))") (class "Default")
      (node (ref "C17") (pin "1") (pinfunction "1_1") (pintype "passive"))
      (node (ref "CR1") (pin "2") (pinfunction "2_2") (pintype "passive"))
      (node (ref "IC5") (pin "9") (pinfunction "PB6(XTAL1/TOSC1/PCI6)_9") (pintype "bidirectional"))
    )
    (net (code "42") (name "Net-(IC5-PB7(XTAL2{slash}TOSC2{slash}PCI7))") (class "Default")
      (node (ref "C16") (pin "1") (pinfunction "1_1") (pintype "passive"))
      (node (ref "CR1") (pin "1") (pinfunction "1_1") (pintype "passive"))
      (node (ref "IC5") (pin "10") (pinfunction "PB7(XTAL2/TOSC2/PCI7)_10") (pintype "bidirectional"))
    )
    (net (code "43") (name "Net-(IC5-PC6({slash}RESET{slash}PCI14))") (class "Default")
      (node (ref "C18") (pin "2") (pinfunction "2_2") (pintype "passive"))
      (node (ref "IC5") (pin "1") (pinfunction "PC6(/RESET/PCI14)_1") (pintype "bidirectional"))
      (node (ref "R14") (pin "2") (pinfunction "2_2") (pintype "passive"))
    )
    (net (code "44") (name "Net-(J3-Pad1)") (class "Default")
      (node (ref "J3") (pin "1") (pinfunction "1_1") (pintype "passive"))
      (node (ref "R5") (pin "1") (pinfunction "1_1") (pintype "passive"))
    )
    (net (code "45") (name "Net-(J3-Pad2)") (class "Default")
      (node (ref "J3") (pin "2") (pinfunction "2_2") (pintype "passive"))
      (node (ref "R6") (pin "1") (pinfunction "1_1") (pintype "passive"))
    )
    (net (code "46") (name "Net-(J3-Pad3)") (class "Default")
      (node (ref "J3") (pin "3") (pinfunction "3_3") (pintype "passive"))
      (node (ref "R7") (pin "1") (pinfunction "1_1") (pintype "passive"))
    )
    (net (code "47") (name "Net-(J3-Pad4)") (class "Default")
      (node (ref "J3") (pin "4") (pinfunction "4_4") (pintype "passive"))
      (node (ref "R8") (pin "1") (pinfunction "1_1") (pintype "passive"))
    )
    (net (code "48") (name "Net-(J3-Pad5)") (class "Default")
      (node (ref "J3") (pin "5") (pinfunction "5_5") (pintype "passive"))
      (node (ref "R9") (pin "1") (pinfunction "1_1") (pintype "passive"))
    )
    (net (code "49") (name "Net-(J3-Pad6)") (class "Default")
      (node (ref "J3") (pin "6") (pinfunction "6_6") (pintype "passive"))
      (node (ref "R10") (pin "1") (pinfunction "1_1") (pintype "passive"))
    )
    (net (code "50") (name "Net-(J3-Pad7)") (class "Default")
      (node (ref "J3") (pin "7") (pinfunction "7_7") (pintype "passive"))
      (node (ref "R11") (pin "1") (pinfunction "1_1") (pintype "passive"))
    )
    (net (code "51") (name "Net-(J3-Pad8)") (class "Default")
      (node (ref "J3") (pin "8") (pinfunction "8_8") (pintype "passive"))
      (node (ref "R12") (pin "1") (pinfunction "1_1") (pintype "passive"))
    )
    (net (code "52") (name "Net-(J9-Pad2)") (class "Default")
      (node (ref "J9") (pin "2") (pinfunction "2_2") (pintype "passive"))
      (node (ref "R16") (pin "2") (pinfunction "2_2") (pintype "passive"))
    )
    (net (code "53") (name "Net-(J9-Pad3)") (class "Default")
      (node (ref "J9") (pin "3") (pinfunction "3_3") (pintype "passive"))
      (node (ref "R15") (pin "2") (pinfunction "2_2") (pintype "passive"))
    )
    (net (code "54") (name "Net-(J9-Pad4)") (class "Default")
      (node (ref "J9") (pin "4") (pinfunction "4_4") (pintype "passive"))
      (node (ref "R13") (pin "2") (pinfunction "2_2") (pintype "passive"))
    )
    (net (code "55") (name "Net-(Q1-PadB)") (class "Default")
      (node (ref "Q1") (pin "B") (pinfunction "B_B") (pintype "passive"))
      (node (ref "R5") (pin "2") (pinfunction "2_2") (pintype "passive"))
    )
    (net (code "56") (name "Net-(Q2-PadB)") (class "Default")
      (node (ref "Q2") (pin "B") (pinfunction "B_B") (pintype "passive"))
      (node (ref "R6") (pin "2") (pinfunction "2_2") (pintype "passive"))
    )
    (net (code "57") (name "Net-(Q3-PadB)") (class "Default")
      (node (ref "Q3") (pin "B") (pinfunction "B_B") (pintype "passive"))
      (node (ref "R7") (pin "2") (pinfunction "2_2") (pintype "passive"))
    )
    (net (code "58") (name "Net-(Q4-PadB)") (class "Default")
      (node (ref "Q4") (pin "B") (pinfunction "B_B") (pintype "passive"))
      (node (ref "R8") (pin "2") (pinfunction "2_2") (pintype "passive"))
    )
    (net (code "59") (name "Net-(Q5-PadB)") (class "Default")
      (node (ref "Q5") (pin "B") (pinfunction "B_B") (pintype "passive"))
      (node (ref "R9") (pin "2") (pinfunction "2_2") (pintype "passive"))
    )
    (net (code "60") (name "Net-(Q6-PadB)") (class "Default")
      (node (ref "Q6") (pin "B") (pinfunction "B_B") (pintype "passive"))
      (node (ref "R10") (pin "2") (pinfunction "2_2") (pintype "passive"))
    )
    (net (code "61") (name "Net-(Q7-PadB)") (class "Default")
      (node (ref "Q7") (pin "B") (pinfunction "B_B") (pintype "passive"))
      (node (ref "R11") (pin "2") (pinfunction "2_2") (pintype "passive"))
    )
    (net (code "62") (name "Net-(Q8-PadB)") (class "Default")
      (node (ref "Q8") (pin "B") (pinfunction "B_B") (pintype "passive"))
      (node (ref "R12") (pin "2") (pinfunction "2_2") (pintype "passive"))
    )
    (net (code "63") (name "Net-(Q9-PadB)") (class "Default")
      (node (ref "Q9") (pin "B") (pinfunction "B_B") (pintype "passive"))
      (node (ref "R17") (pin "2") (pinfunction "2_2") (pintype "passive"))
    )
    (net (code "64") (name "Net-(Q10-PadB)") (class "Default")
      (node (ref "Q10") (pin "B") (pinfunction "B_B") (pintype "passive"))
      (node (ref "R18") (pin "2") (pinfunction "2_2") (pintype "passive"))
    )
    (net (code "65") (name "Net-(Q11-PadB)") (class "Default")
      (node (ref "Q11") (pin "B") (pinfunction "B_B") (pintype "passive"))
      (node (ref "R13") (pin "1") (pinfunction "1_1") (pintype "passive"))
    )
    (net (code "66") (name "Net-(Q12-PadB)") (class "Default")
      (node (ref "Q12") (pin "B") (pinfunction "B_B") (pintype "passive"))
      (node (ref "R15") (pin "1") (pinfunction "1_1") (pintype "passive"))
    )
    (net (code "67") (name "Net-(Q13-PadB)") (class "Default")
      (node (ref "Q13") (pin "B") (pinfunction "B_B") (pintype "passive"))
      (node (ref "R16") (pin "1") (pinfunction "1_1") (pintype "passive"))
    )
    (net (code "68") (name "Net-(R1-Pad1)") (class "Default")
      (node (ref "R1") (pin "1") (pinfunction "1_1") (pintype "passive"))
      (node (ref "U$2") (pin "RST") (pinfunction "RST_RST") (pintype "bidirectional"))
    )
    (net (code "69") (name "Net-(X1B-KL)") (class "Default")
      (node (ref "K8") (pin "S") (pinfunction "S_S") (pintype "passive"))
      (node (ref "X1") (pin "2") (pinfunction "KL_2") (pintype "passive"))
    )
    (net (code "70") (name "Net-(X1C-KL)") (class "Default")
      (node (ref "K7") (pin "S") (pinfunction "S_S") (pintype "passive"))
      (node (ref "X1") (pin "3") (pinfunction "KL_3") (pintype "passive"))
    )
    (net (code "71") (name "Net-(X1D-KL)") (class "Default")
      (node (ref "K6") (pin "S") (pinfunction "S_S") (pintype "passive"))
      (node (ref "X1") (pin "4") (pinfunction "KL_4") (pintype "passive"))
    )
    (net (code "72") (name "Net-(X1E-KL)") (class "Default")
      (node (ref "K5") (pin "S") (pinfunction "S_S") (pintype "passive"))
      (node (ref "X1") (pin "5") (pinfunction "KL_5") (pintype "passive"))
    )
    (net (code "73") (name "Net-(X1F-KL)") (class "Default")
      (node (ref "K4") (pin "S") (pinfunction "S_S") (pintype "passive"))
      (node (ref "X1") (pin "6") (pinfunction "KL_6") (pintype "passive"))
    )
    (net (code "74") (name "Net-(X1G-KL)") (class "Default")
      (node (ref "K3") (pin "S") (pinfunction "S_S") (pintype "passive"))
      (node (ref "X1") (pin "7") (pinfunction "KL_7") (pintype "passive"))
    )
    (net (code "75") (name "Net-(X1H-KL)") (class "Default")
      (node (ref "K2") (pin "S") (pinfunction "S_S") (pintype "passive"))
      (node (ref "X1") (pin "8") (pinfunction "KL_8") (pintype "passive"))
    )
    (net (code "76") (name "Net-(X1I-KL)") (class "Default")
      (node (ref "K1") (pin "S") (pinfunction "S_S") (pintype "passive"))
      (node (ref "X1") (pin "9") (pinfunction "KL_9") (pintype "passive"))
    )
    (net (code "77") (name "Net-(X2A-KL)") (class "Default")
      (node (ref "K10") (pin "P") (pinfunction "P_P") (pintype "passive"))
      (node (ref "K11") (pin "P") (pinfunction "P_P") (pintype "passive"))
      (node (ref "K9") (pin "P") (pinfunction "P_P") (pintype "passive"))
      (node (ref "X2") (pin "1") (pinfunction "KL_1") (pintype "passive"))
    )
    (net (code "78") (name "Net-(X2B-KL)") (class "Default")
      (node (ref "K11") (pin "S") (pinfunction "S_S") (pintype "passive"))
      (node (ref "X2") (pin "2") (pinfunction "KL_2") (pintype "passive"))
    )
    (net (code "79") (name "Net-(X2C-KL)") (class "Default")
      (node (ref "K10") (pin "S") (pinfunction "S_S") (pintype "passive"))
      (node (ref "X2") (pin "3") (pinfunction "KL_3") (pintype "passive"))
    )
    (net (code "80") (name "Net-(X2D-KL)") (class "Default")
      (node (ref "K9") (pin "S") (pinfunction "S_S") (pintype "passive"))
      (node (ref "X2") (pin "4") (pinfunction "KL_4") (pintype "passive"))
    )
    (net (code "81") (name "PIR") (class "Default")
      (node (ref "J11") (pin "2") (pinfunction "2_2") (pintype "passive"))
      (node (ref "R18") (pin "1") (pinfunction "1_1") (pintype "passive"))
    )
    (net (code "82") (name "PRX") (class "Default")
      (node (ref "IC1") (pin "3") (pinfunction "(PCI17/TXD)PD1_3") (pintype "bidirectional"))
      (node (ref "J1") (pin "5") (pinfunction "5_5") (pintype "passive"))
    )
    (net (code "83") (name "PRX2") (class "Default")
      (node (ref "IC5") (pin "3") (pinfunction "(PCI17/TXD)PD1_3") (pintype "bidirectional"))
      (node (ref "J6") (pin "5") (pinfunction "5_5") (pintype "passive"))
    )
    (net (code "84") (name "PTX+SWS") (class "Default")
      (node (ref "IC1") (pin "2") (pinfunction "(PCI16/RXD)PD0_2") (pintype "bidirectional"))
      (node (ref "IC4") (pin "5") (pinfunction "Y_5") (pintype "output"))
      (node (ref "J1") (pin "4") (pinfunction "4_4") (pintype "passive"))
      (node (ref "R3") (pin "2") (pinfunction "2_2") (pintype "passive"))
    )
    (net (code "85") (name "PTX2") (class "Default")
      (node (ref "IC5") (pin "2") (pinfunction "(PCI16/RXD)PD0_2") (pintype "bidirectional"))
      (node (ref "J6") (pin "4") (pinfunction "4_4") (pintype "passive"))
    )
    (net (code "86") (name "RELAY1") (class "Default")
      (node (ref "IC1") (pin "4") (pinfunction "(PCI18/INT0)PD2_4") (pintype "bidirectional"))
      (node (ref "J2") (pin "9") (pinfunction "9_9") (pintype "passive"))
    )
    (net (code "87") (name "RELAY2") (class "Default")
      (node (ref "IC1") (pin "5") (pinfunction "(PCI19/INT1/OC2B)PD3_5") (pintype "bidirectional"))
      (node (ref "J2") (pin "8") (pinfunction "8_8") (pintype "passive"))
    )
    (net (code "88") (name "RELAY3") (class "Default")
      (node (ref "IC1") (pin "28") (pinfunction "(PCI13/ADC5/SCL)PC5_28") (pintype "bidirectional"))
      (node (ref "J2") (pin "7") (pinfunction "7_7") (pintype "passive"))
    )
    (net (code "89") (name "RELAY4") (class "Default")
      (node (ref "IC1") (pin "27") (pinfunction "(PCI12/ADC4/SDA)PC4_27") (pintype "bidirectional"))
      (node (ref "J2") (pin "6") (pinfunction "6_6") (pintype "passive"))
    )
    (net (code "90") (name "RELAY5") (class "Default")
      (node (ref "IC1") (pin "26") (pinfunction "(PCI11/ADC3)PC3_26") (pintype "bidirectional"))
      (node (ref "J2") (pin "5") (pinfunction "5_5") (pintype "passive"))
    )
    (net (code "91") (name "RELAY6") (class "Default")
      (node (ref "IC1") (pin "25") (pinfunction "(PCI10/ADC2)PC2_25") (pintype "bidirectional"))
      (node (ref "J2") (pin "4") (pinfunction "4_4") (pintype "passive"))
    )
    (net (code "92") (name "RELAY7") (class "Default")
      (node (ref "IC1") (pin "24") (pinfunction "(PCI9/ADC1)PC1_24") (pintype "bidirectional"))
      (node (ref "J2") (pin "3") (pinfunction "3_3") (pintype "passive"))
    )
    (net (code "93") (name "RELAY8") (class "Default")
      (node (ref "IC1") (pin "23") (pinfunction "(PCI8/ADC0)PC0_23") (pintype "bidirectional"))
      (node (ref "J2") (pin "2") (pinfunction "2_2") (pintype "passive"))
    )
    (net (code "94") (name "RELAY21") (class "Default")
      (node (ref "IC5") (pin "28") (pinfunction "(PCI13/ADC5/SCL)PC5_28") (pintype "bidirectional"))
      (node (ref "J7") (pin "4") (pinfunction "4_4") (pintype "passive"))
    )
    (net (code "95") (name "RELAY22") (class "Default")
      (node (ref "IC5") (pin "27") (pinfunction "(PCI12/ADC4/SDA)PC4_27") (pintype "bidirectional"))
      (node (ref "J7") (pin "3") (pinfunction "3_3") (pintype "passive"))
    )
    (net (code "96") (name "RELAY23") (class "Default")
      (node (ref "IC5") (pin "26") (pinfunction "(PCI11/ADC3)PC3_26") (pintype "bidirectional"))
      (node (ref "J7") (pin "2") (pinfunction "2_2") (pintype "passive"))
    )
    (net (code "97") (name "RELAY24") (class "Default")
      (node (ref "IC5") (pin "25") (pinfunction "(PCI10/ADC2)PC2_25") (pintype "bidirectional"))
      (node (ref "J8") (pin "4") (pinfunction "4_4") (pintype "passive"))
    )
    (net (code "98") (name "RELAY25") (class "Default")
      (node (ref "IC5") (pin "24") (pinfunction "(PCI9/ADC1)PC1_24") (pintype "bidirectional"))
      (node (ref "J8") (pin "3") (pinfunction "3_3") (pintype "passive"))
    )
    (net (code "99") (name "RELAY26") (class "Default")
      (node (ref "IC5") (pin "23") (pinfunction "(PCI8/ADC0)PC0_23") (pintype "bidirectional"))
      (node (ref "J8") (pin "2") (pinfunction "2_2") (pintype "passive"))
    )
    (net (code "100") (name "RX") (class "Default")
      (node (ref "IC1") (pin "11") (pinfunction "(PCI21/T1/OC0B)PD5_11") (pintype "bidirectional"))
      (node (ref "U$2") (pin "RX") (pinfunction "RXD_RX") (pintype "bidirectional"))
    )
    (net (code "101") (name "S1") (class "Default")
      (node (ref "IC1") (pin "12") (pinfunction "(PCI22/AIN0OC0A)PD6_12") (pintype "bidirectional"))
      (node (ref "IC4") (pin "11") (pinfunction "A_11") (pintype "input"))
    )
    (net (code "102") (name "S2") (class "Default")
      (node (ref "IC1") (pin "13") (pinfunction "(PCI23/AIN1)PD7_13") (pintype "bidirectional"))
      (node (ref "IC4") (pin "10") (pinfunction "B_10") (pintype "input"))
    )
    (net (code "103") (name "S3") (class "Default")
      (node (ref "IC1") (pin "14") (pinfunction "(PCI0/ICP/CLKO)PB0_14") (pintype "bidirectional"))
      (node (ref "IC4") (pin "9") (pinfunction "C_9") (pintype "input"))
    )
    (net (code "104") (name "S21") (class "Default")
      (node (ref "IC5") (pin "5") (pinfunction "(PCI19/INT1/OC2B)PD3_5") (pintype "bidirectional"))
      (node (ref "RN1") (pin "2") (pinfunction "2_2") (pintype "passive"))
      (node (ref "X4") (pin "1") (pinfunction "KL_1") (pintype "passive"))
    )
    (net (code "105") (name "S22") (class "Default")
      (node (ref "IC5") (pin "6") (pinfunction "(PCI20/XCK/T0)PD4_6") (pintype "bidirectional"))
      (node (ref "RN1") (pin "3") (pinfunction "3_3") (pintype "passive"))
      (node (ref "X4") (pin "2") (pinfunction "KL_2") (pintype "passive"))
    )
    (net (code "106") (name "S23") (class "Default")
      (node (ref "IC5") (pin "11") (pinfunction "(PCI21/T1/OC0B)PD5_11") (pintype "bidirectional"))
      (node (ref "RN1") (pin "4") (pinfunction "4_4") (pintype "passive"))
      (node (ref "X4") (pin "3") (pinfunction "KL_3") (pintype "passive"))
    )
    (net (code "107") (name "S24") (class "Default")
      (node (ref "IC5") (pin "12") (pinfunction "(PCI22/AIN0OC0A)PD6_12") (pintype "bidirectional"))
      (node (ref "RN1") (pin "5") (pinfunction "5_5") (pintype "passive"))
      (node (ref "X4") (pin "4") (pinfunction "KL_4") (pintype "passive"))
    )
    (net (code "108") (name "S25") (class "Default")
      (node (ref "IC5") (pin "13") (pinfunction "(PCI23/AIN1)PD7_13") (pintype "bidirectional"))
      (node (ref "RN1") (pin "6") (pinfunction "6_6") (pintype "passive"))
      (node (ref "X4") (pin "5") (pinfunction "KL_5") (pintype "passive"))
    )
    (net (code "109") (name "S26") (class "Default")
      (node (ref "IC5") (pin "14") (pinfunction "(PCI0/ICP/CLKO)PB0_14") (pintype "bidirectional"))
      (node (ref "RN1") (pin "7") (pinfunction "7_7") (pintype "passive"))
      (node (ref "X4") (pin "6") (pinfunction "KL_6") (pintype "passive"))
    )
    (net (code "110") (name "SCK") (class "Default")
      (node (ref "IC1") (pin "19") (pinfunction "(PCI5/SCK)PB5_19") (pintype "bidirectional"))
      (node (ref "U$1") (pin "SCK") (pinfunction "SCK_SCK") (pintype "bidirectional"))
    )
    (net (code "111") (name "SCK2") (class "Default")
      (node (ref "IC5") (pin "19") (pinfunction "(PCI5/SCK)PB5_19") (pintype "bidirectional"))
      (node (ref "U$3") (pin "SCK") (pinfunction "SCK_SCK") (pintype "bidirectional"))
    )
    (net (code "112") (name "SW1") (class "Default")
      (node (ref "IC4") (pin "15") (pinfunction "D4_15") (pintype "input"))
      (node (ref "IC7") (pin "3") (pinfunction "O_3") (pintype "output"))
      (node (ref "R20") (pin "2") (pinfunction "2_2") (pintype "passive"))
    )
    (net (code "113") (name "SW2") (class "Default")
      (node (ref "IC4") (pin "14") (pinfunction "D5_14") (pintype "input"))
      (node (ref "IC7") (pin "6") (pinfunction "O_6") (pintype "output"))
      (node (ref "R21") (pin "1") (pinfunction "1_1") (pintype "passive"))
    )
    (net (code "114") (name "SW3") (class "Default")
      (node (ref "IC4") (pin "1") (pinfunction "D3_1") (pintype "input"))
      (node (ref "RN3") (pin "2") (pinfunction "2_2") (pintype "passive"))
      (node (ref "X3") (pin "5") (pinfunction "KL_5") (pintype "passive"))
    )
    (net (code "115") (name "SW4") (class "Default")
      (node (ref "IC4") (pin "2") (pinfunction "D2_2") (pintype "input"))
      (node (ref "RN3") (pin "3") (pinfunction "3_3") (pintype "passive"))
      (node (ref "X3") (pin "6") (pinfunction "KL_6") (pintype "passive"))
    )
    (net (code "116") (name "SW5") (class "Default")
      (node (ref "IC4") (pin "3") (pinfunction "D1_3") (pintype "input"))
      (node (ref "RN3") (pin "4") (pinfunction "4_4") (pintype "passive"))
      (node (ref "X3") (pin "7") (pinfunction "KL_7") (pintype "passive"))
    )
    (net (code "117") (name "SW6") (class "Default")
      (node (ref "IC4") (pin "4") (pinfunction "D0_4") (pintype "input"))
      (node (ref "RN3") (pin "5") (pinfunction "5_5") (pintype "passive"))
      (node (ref "X3") (pin "8") (pinfunction "KL_8") (pintype "passive"))
    )
    (net (code "118") (name "SW7") (class "Default")
      (node (ref "IC4") (pin "13") (pinfunction "D6_13") (pintype "input"))
      (node (ref "RN3") (pin "6") (pinfunction "6_6") (pintype "passive"))
      (node (ref "X3") (pin "9") (pinfunction "KL_9") (pintype "passive"))
    )
    (net (code "119") (name "SW8") (class "Default")
      (node (ref "IC4") (pin "12") (pinfunction "D7_12") (pintype "input"))
      (node (ref "RN3") (pin "7") (pinfunction "7_7") (pintype "passive"))
      (node (ref "X3") (pin "10") (pinfunction "KL_10") (pintype "passive"))
    )
    (net (code "120") (name "TSW1") (class "Default")
      (node (ref "IC7") (pin "4") (pinfunction "I0_4") (pintype "input"))
      (node (ref "RN2") (pin "4") (pinfunction "4_4") (pintype "passive"))
      (node (ref "X3") (pin "3") (pinfunction "KL_3") (pintype "passive"))
    )
    (net (code "121") (name "TSW2") (class "Default")
      (node (ref "IC7") (pin "5") (pinfunction "I1_5") (pintype "input"))
      (node (ref "RN2") (pin "5") (pinfunction "5_5") (pintype "passive"))
      (node (ref "X3") (pin "4") (pinfunction "KL_4") (pintype "passive"))
    )
    (net (code "122") (name "TX") (class "Default")
      (node (ref "IC1") (pin "6") (pinfunction "(PCI20/XCK/T0)PD4_6") (pintype "bidirectional"))
      (node (ref "U$2") (pin "TX") (pinfunction "TXD_TX") (pintype "bidirectional"))
    )
    (net (code "123") (name "unconnected-(IC1-AREF-Pad21)") (class "Default")
      (node (ref "IC1") (pin "21") (pinfunction "AREF_21") (pintype "bidirectional"))
    )
    (net (code "124") (name "unconnected-(IC1-GND-Pad8)") (class "Default")
      (node (ref "IC1") (pin "8") (pinfunction "GND_8") (pintype "bidirectional"))
    )
    (net (code "125") (name "unconnected-(IC4A-W-Pad6)") (class "Default")
      (node (ref "IC4") (pin "6") (pinfunction "W_6") (pintype "output"))
    )
    (net (code "126") (name "unconnected-(IC5-AREF-Pad21)") (class "Default")
      (node (ref "IC5") (pin "21") (pinfunction "AREF_21") (pintype "bidirectional"))
    )
    (net (code "127") (name "unconnected-(IC5-GND-Pad8)") (class "Default")
      (node (ref "IC5") (pin "8") (pinfunction "GND_8") (pintype "bidirectional"))
    )
    (net (code "128") (name "unconnected-(J1-Pad2)") (class "Default")
      (node (ref "J1") (pin "2") (pinfunction "2_2") (pintype "passive"))
    )
    (net (code "129") (name "unconnected-(J6-Pad2)") (class "Default")
      (node (ref "J6") (pin "2") (pinfunction "2_2") (pintype "passive"))
    )
    (net (code "130") (name "unconnected-(K1-PadO)") (class "Default")
      (node (ref "K1") (pin "O") (pinfunction "O_O") (pintype "passive"))
    )
    (net (code "131") (name "unconnected-(K2-PadO)") (class "Default")
      (node (ref "K2") (pin "O") (pinfunction "O_O") (pintype "passive"))
    )
    (net (code "132") (name "unconnected-(K3-PadO)") (class "Default")
      (node (ref "K3") (pin "O") (pinfunction "O_O") (pintype "passive"))
    )
    (net (code "133") (name "unconnected-(K4-PadO)") (class "Default")
      (node (ref "K4") (pin "O") (pinfunction "O_O") (pintype "passive"))
    )
    (net (code "134") (name "unconnected-(K5-PadO)") (class "Default")
      (node (ref "K5") (pin "O") (pinfunction "O_O") (pintype "passive"))
    )
    (net (code "135") (name "unconnected-(K6-PadO)") (class "Default")
      (node (ref "K6") (pin "O") (pinfunction "O_O") (pintype "passive"))
    )
    (net (code "136") (name "unconnected-(K7-PadO)") (class "Default")
      (node (ref "K7") (pin "O") (pinfunction "O_O") (pintype "passive"))
    )
    (net (code "137") (name "unconnected-(K8-PadO)") (class "Default")
      (node (ref "K8") (pin "O") (pinfunction "O_O") (pintype "passive"))
    )
    (net (code "138") (name "unconnected-(K9-PadO)") (class "Default")
      (node (ref "K9") (pin "O") (pinfunction "O_O") (pintype "passive"))
    )
    (net (code "139") (name "unconnected-(K10-PadO)") (class "Default")
      (node (ref "K10") (pin "O") (pinfunction "O_O") (pintype "passive"))
    )
    (net (code "140") (name "unconnected-(K11-PadO)") (class "Default")
      (node (ref "K11") (pin "O") (pinfunction "O_O") (pintype "passive"))
    )
    (net (code "141") (name "unconnected-(U$1-PadIRQ)") (class "Default")
      (node (ref "U$1") (pin "IRQ") (pinfunction "IRQ_IRQ") (pintype "bidirectional"))
    )
    (net (code "142") (name "unconnected-(U$2-PadGPIO0)") (class "Default")
      (node (ref "U$2") (pin "GPIO0") (pinfunction "GPIO0_GPIO0") (pintype "bidirectional"))
    )
    (net (code "143") (name "unconnected-(U$2-PadGPIO2)") (class "Default")
      (node (ref "U$2") (pin "GPIO2") (pinfunction "GPIO2_GPIO2") (pintype "bidirectional"))
    )
  )
)
